# arduino_uno_pcb__with_lcd.net
KiCad netlist of a schematic drawn in EAGLE
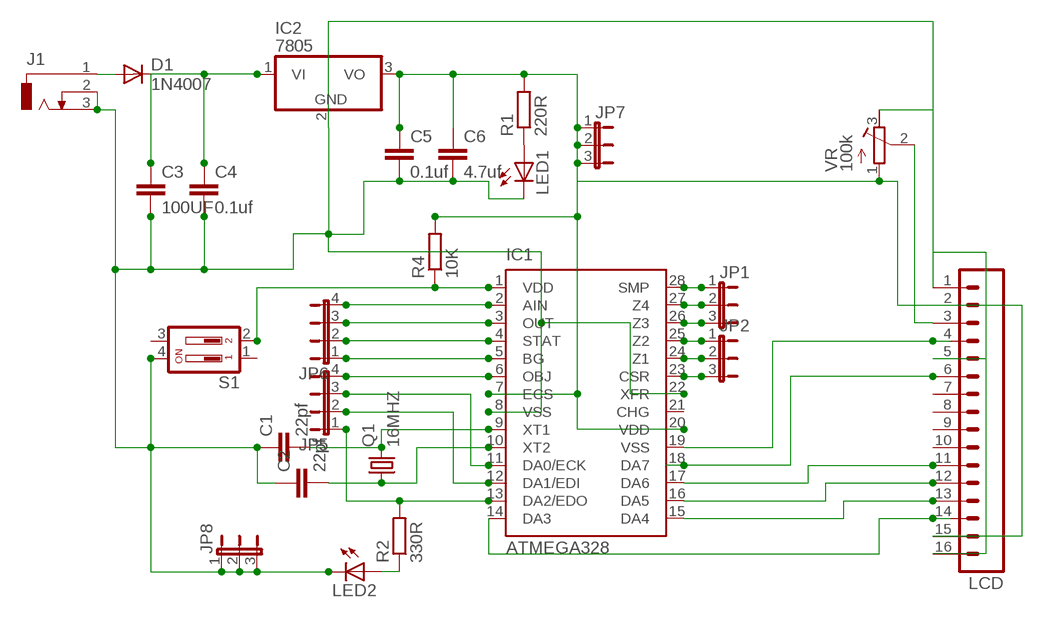
[diagram p0: schematic, sheet 1]

(export (version "E")
  (design (tool "Eeschema 10.0.6"))
  (components
    (comp (ref "C1")
      (value "22pf")
      (footprint "eagle-import:C2.5-2")
      (libsource (lib "eagle-import") (part "C2.5/2"))
    )
    (comp (ref "C2")
      (value "22pf")
      (footprint "eagle-import:C2.5-2")
      (libsource (lib "eagle-import") (part "C2.5/2"))
    )
    (comp (ref "C3")
      (value "100UF")
      (footprint "eagle-import:C2.5-2")
      (libsource (lib "eagle-import") (part "C2.5/2"))
    )
    (comp (ref "C4")
      (value "0.1uf")
      (footprint "eagle-import:C2.5-2")
      (libsource (lib "eagle-import") (part "C2.5/2"))
    )
    (comp (ref "C5")
      (value "0.1uf")
      (footprint "eagle-import:C2.5-2")
      (libsource (lib "eagle-import") (part "C2.5/2"))
    )
    (comp (ref "C6")
      (value "4.7uf")
      (footprint "eagle-import:C2.5-2")
      (libsource (lib "eagle-import") (part "C2.5/2"))
    )
    (comp (ref "D1")
      (value "1N4007")
      (footprint "eagle-import:DO41-10")
      (libsource (lib "eagle-import") (part "1N4004"))
    )
    (comp (ref "IC1")
      (value "ATMEGA328")
      (footprint "eagle-import:DIL28-3")
      (libsource (lib "eagle-import") (part "QT9701BD"))
    )
    (comp (ref "IC2")
      (value "7805")
      (footprint "eagle-import:TO220V")
      (libsource (lib "eagle-import") (part "78TV6"))
    )
    (comp (ref "J1")
      (value "DCJ0303")
      (footprint "eagle-import:DCJ0303")
      (libsource (lib "eagle-import") (part "DCJ0303"))
    )
    (comp (ref "JP1")
      (value "JP2E")
      (footprint "eagle-import:JP2")
      (libsource (lib "eagle-import") (part "JP2E"))
    )
    (comp (ref "JP2")
      (value "JP2E")
      (footprint "eagle-import:JP2")
      (libsource (lib "eagle-import") (part "JP2E"))
    )
    (comp (ref "JP5")
      (value "JP4E")
      (footprint "eagle-import:JP4")
      (libsource (lib "eagle-import") (part "JP4E"))
    )
    (comp (ref "JP6")
      (value "JP4E")
      (footprint "eagle-import:JP4")
      (libsource (lib "eagle-import") (part "JP4E"))
    )
    (comp (ref "JP7")
      (value "JP2E")
      (footprint "eagle-import:JP2")
      (libsource (lib "eagle-import") (part "JP2E"))
    )
    (comp (ref "JP8")
      (value "JP2E")
      (footprint "eagle-import:JP2")
      (libsource (lib "eagle-import") (part "JP2E"))
    )
    (comp (ref "LCD")
      (value "M16")
      (footprint "eagle-import:16P")
      (libsource (lib "eagle-import") (part "M16"))
    )
    (comp (ref "LED1")
      (value "LED3MM")
      (footprint "eagle-import:LED3MM")
      (libsource (lib "eagle-import") (part "LED3MM"))
    )
    (comp (ref "LED2")
      (value "LED3MM")
      (footprint "eagle-import:LED3MM")
      (libsource (lib "eagle-import") (part "LED3MM"))
    )
    (comp (ref "Q1")
      (value "16MHZ")
      (footprint "eagle-import:HC49_S")
      (libsource (lib "eagle-import") (part "CRYSTALHC49S"))
    )
    (comp (ref "R1")
      (value "220R")
      (footprint "eagle-import:0207_10")
      (libsource (lib "eagle-import") (part "R-EU_0207/10"))
    )
    (comp (ref "R2")
      (value "330R")
      (footprint "eagle-import:0207_10")
      (libsource (lib "eagle-import") (part "R-EU_0207/10"))
    )
    (comp (ref "R4")
      (value "10K")
      (footprint "eagle-import:0207_10")
      (libsource (lib "eagle-import") (part "R-EU_0207/10"))
    )
    (comp (ref "S1")
      (value "DP02")
      (footprint "eagle-import:DP-02")
      (fields (field (name "MPN") "MCDP02"))
      (libsource (lib "eagle-import") (part "DP02"))
    )
    (comp (ref "VR")
      (value "100k")
      (footprint "eagle-import:RTRIM64P")
      (libsource (lib "eagle-import") (part "R-TRIMM64P"))
    )
  )
  (nets
    (net (code "1") (name "Net-(D1-PadA)") (class "Default")
      (node (ref "D1") (pin "A") (pinfunction "A_A") (pintype "passive"))
      (node (ref "J1") (pin "1") (pinfunction "1_1") (pintype "passive"))
    )
    (net (code "2") (name "Net-(IC1-AIN)") (class "Default")
      (node (ref "IC1") (pin "2") (pinfunction "AIN_2") (pintype "input"))
      (node (ref "JP6") (pin "4") (pinfunction "4_4") (pintype "passive"))
    )
    (net (code "3") (name "Net-(IC1-BG)") (class "Default")
      (node (ref "IC1") (pin "5") (pinfunction "BG_5") (pintype "input"))
      (node (ref "JP6") (pin "1") (pinfunction "1_1") (pintype "passive"))
    )
    (net (code "4") (name "Net-(IC1-CSR)") (class "Default")
      (node (ref "IC1") (pin "23") (pinfunction "CSR_23") (pintype "output"))
      (node (ref "JP2") (pin "3") (pinfunction "3_3") (pintype "passive"))
    )
    (net (code "5") (name "Net-(IC1-DA0{slash}ECK)") (class "Default")
      (node (ref "IC1") (pin "11") (pinfunction "DA0/ECK_11") (pintype "output"))
      (node (ref "JP5") (pin "3") (pinfunction "3_3") (pintype "passive"))
    )
    (net (code "6") (name "Net-(IC1-DA1{slash}EDI)") (class "Default")
      (node (ref "IC1") (pin "12") (pinfunction "DA1/EDI_12") (pintype "output"))
      (node (ref "JP5") (pin "2") (pinfunction "2_2") (pintype "passive"))
    )
    (net (code "7") (name "Net-(IC1-DA2{slash}EDO)") (class "Default")
      (node (ref "IC1") (pin "13") (pinfunction "DA2/EDO_13") (pintype "output"))
      (node (ref "JP5") (pin "1") (pinfunction "1_1") (pintype "passive"))
      (node (ref "R2") (pin "2") (pinfunction "2_2") (pintype "passive"))
    )
    (net (code "8") (name "Net-(IC1-DA3)") (class "Default")
      (node (ref "IC1") (pin "14") (pinfunction "DA3_14") (pintype "output"))
      (node (ref "LCD") (pin "14") (pinfunction "14_14") (pintype "passive"))
    )
    (net (code "9") (name "Net-(IC1-DA4)") (class "Default")
      (node (ref "IC1") (pin "15") (pinfunction "DA4_15") (pintype "output"))
      (node (ref "LCD") (pin "13") (pinfunction "13_13") (pintype "passive"))
    )
    (net (code "10") (name "Net-(IC1-DA5)") (class "Default")
      (node (ref "IC1") (pin "16") (pinfunction "DA5_16") (pintype "output"))
      (node (ref "LCD") (pin "12") (pinfunction "12_12") (pintype "passive"))
    )
    (net (code "11") (name "Net-(IC1-DA6)") (class "Default")
      (node (ref "IC1") (pin "17") (pinfunction "DA6_17") (pintype "output"))
      (node (ref "LCD") (pin "11") (pinfunction "11_11") (pintype "passive"))
    )
    (net (code "12") (name "Net-(IC1-DA7)") (class "Default")
      (node (ref "IC1") (pin "18") (pinfunction "DA7_18") (pintype "output"))
      (node (ref "LCD") (pin "6") (pinfunction "6_6") (pintype "passive"))
    )
    (net (code "13") (name "Net-(IC1-ECS)") (class "Default")
      (node (ref "C5") (pin "1") (pinfunction "1_1") (pintype "passive"))
      (node (ref "C6") (pin "1") (pinfunction "1_1") (pintype "passive"))
      (node (ref "IC1") (pin "20") (pinfunction "VDD_20") (pintype "input"))
      (node (ref "IC1") (pin "7") (pinfunction "ECS_7") (pintype "output"))
      (node (ref "IC2") (pin "3") (pinfunction "VO_3") (pintype "passive"))
      (node (ref "JP7") (pin "1") (pinfunction "1_1") (pintype "passive"))
      (node (ref "JP7") (pin "2") (pinfunction "2_2") (pintype "passive"))
      (node (ref "JP7") (pin "3") (pinfunction "3_3") (pintype "passive"))
      (node (ref "LCD") (pin "15") (pinfunction "15_15") (pintype "passive"))
      (node (ref "R1") (pin "2") (pinfunction "2_2") (pintype "passive"))
      (node (ref "R4") (pin "2") (pinfunction "2_2") (pintype "passive"))
      (node (ref "VR") (pin "1") (pinfunction "E_1") (pintype "passive"))
    )
    (net (code "14") (name "Net-(IC1-OBJ)") (class "Default")
      (node (ref "IC1") (pin "6") (pinfunction "OBJ_6") (pintype "input"))
      (node (ref "JP5") (pin "4") (pinfunction "4_4") (pintype "passive"))
    )
    (net (code "15") (name "Net-(IC1-OUT)") (class "Default")
      (node (ref "IC1") (pin "3") (pinfunction "OUT_3") (pintype "output"))
      (node (ref "JP6") (pin "3") (pinfunction "3_3") (pintype "passive"))
    )
    (net (code "16") (name "Net-(IC1-SMP)") (class "Default")
      (node (ref "IC1") (pin "28") (pinfunction "SMP_28") (pintype "output"))
      (node (ref "JP1") (pin "1") (pinfunction "1_1") (pintype "passive"))
    )
    (net (code "17") (name "Net-(IC1-STAT)") (class "Default")
      (node (ref "IC1") (pin "4") (pinfunction "STAT_4") (pintype "output"))
      (node (ref "JP6") (pin "2") (pinfunction "2_2") (pintype "passive"))
    )
    (net (code "18") (name "Net-(IC1-VDD-Pad1)") (class "Default")
      (node (ref "IC1") (pin "1") (pinfunction "VDD_1") (pintype "input"))
      (node (ref "R4") (pin "1") (pinfunction "1_1") (pintype "passive"))
      (node (ref "S1") (pin "2") (pinfunction "2_2") (pintype "passive"))
    )
    (net (code "19") (name "Net-(IC1-VSS-Pad19)") (class "Default")
      (node (ref "IC1") (pin "19") (pinfunction "VSS_19") (pintype "input"))
      (node (ref "LCD") (pin "4") (pinfunction "4_4") (pintype "passive"))
    )
    (net (code "20") (name "Net-(IC1-XFR)") (class "Default")
      (node (ref "C1") (pin "1") (pinfunction "1_1") (pintype "passive"))
      (node (ref "C2") (pin "1") (pinfunction "1_1") (pintype "passive"))
      (node (ref "C3") (pin "2") (pinfunction "2_2") (pintype "passive"))
      (node (ref "C4") (pin "2") (pinfunction "2_2") (pintype "passive"))
      (node (ref "C5") (pin "2") (pinfunction "2_2") (pintype "passive"))
      (node (ref "C6") (pin "2") (pinfunction "2_2") (pintype "passive"))
      (node (ref "IC1") (pin "22") (pinfunction "XFR_22") (pintype "output"))
      (node (ref "IC1") (pin "8") (pinfunction "VSS_8") (pintype "input"))
      (node (ref "IC2") (pin "2") (pinfunction "GND_2") (pintype "passive"))
      (node (ref "J1") (pin "2") (pinfunction "2_2") (pintype "passive"))
      (node (ref "J1") (pin "3") (pinfunction "3_3") (pintype "passive"))
      (node (ref "JP8") (pin "1") (pinfunction "1_1") (pintype "passive"))
      (node (ref "JP8") (pin "2") (pinfunction "2_2") (pintype "passive"))
      (node (ref "JP8") (pin "3") (pinfunction "3_3") (pintype "passive"))
      (node (ref "LCD") (pin "1") (pinfunction "1_1") (pintype "passive"))
      (node (ref "LCD") (pin "16") (pinfunction "16_16") (pintype "passive"))
      (node (ref "LCD") (pin "5") (pinfunction "5_5") (pintype "passive"))
      (node (ref "LED1") (pin "K") (pinfunction "C_K") (pintype "passive"))
      (node (ref "LED2") (pin "K") (pinfunction "C_K") (pintype "passive"))
      (node (ref "S1") (pin "4") (pinfunction "4_4") (pintype "passive"))
      (node (ref "VR") (pin "3") (pinfunction "A_3") (pintype "passive"))
    )
    (net (code "21") (name "Net-(IC1-XT1)") (class "Default")
      (node (ref "C1") (pin "2") (pinfunction "2_2") (pintype "passive"))
      (node (ref "IC1") (pin "9") (pinfunction "XT1_9") (pintype "input"))
      (node (ref "Q1") (pin "2") (pinfunction "2_2") (pintype "passive"))
    )
    (net (code "22") (name "Net-(IC1-XT2)") (class "Default")
      (node (ref "C2") (pin "2") (pinfunction "2_2") (pintype "passive"))
      (node (ref "IC1") (pin "10") (pinfunction "XT2_10") (pintype "output"))
      (node (ref "Q1") (pin "1") (pinfunction "1_1") (pintype "passive"))
    )
    (net (code "23") (name "Net-(IC1-Z1)") (class "Default")
      (node (ref "IC1") (pin "24") (pinfunction "Z1_24") (pintype "output"))
      (node (ref "JP2") (pin "2") (pinfunction "2_2") (pintype "passive"))
    )
    (net (code "24") (name "Net-(IC1-Z2)") (class "Default")
      (node (ref "IC1") (pin "25") (pinfunction "Z2_25") (pintype "output"))
      (node (ref "JP2") (pin "1") (pinfunction "1_1") (pintype "passive"))
    )
    (net (code "25") (name "Net-(IC1-Z3)") (class "Default")
      (node (ref "IC1") (pin "26") (pinfunction "Z3_26") (pintype "output"))
      (node (ref "JP1") (pin "3") (pinfunction "3_3") (pintype "passive"))
    )
    (net (code "26") (name "Net-(IC1-Z4)") (class "Default")
      (node (ref "IC1") (pin "27") (pinfunction "Z4_27") (pintype "output"))
      (node (ref "JP1") (pin "2") (pinfunction "2_2") (pintype "passive"))
    )
    (net (code "27") (name "Net-(IC2-VI)") (class "Default")
      (node (ref "C3") (pin "1") (pinfunction "1_1") (pintype "passive"))
      (node (ref "C4") (pin "1") (pinfunction "1_1") (pintype "passive"))
      (node (ref "D1") (pin "C") (pinfunction "C_C") (pintype "passive"))
      (node (ref "IC2") (pin "1") (pinfunction "VI_1") (pintype "input"))
    )
    (net (code "28") (name "Net-(LED1-PadA)") (class "Default")
      (node (ref "LED1") (pin "A") (pinfunction "A_A") (pintype "passive"))
      (node (ref "R1") (pin "1") (pinfunction "1_1") (pintype "passive"))
    )
    (net (code "29") (name "Net-(LED2-PadA)") (class "Default")
      (node (ref "LED2") (pin "A") (pinfunction "A_A") (pintype "passive"))
      (node (ref "R2") (pin "1") (pinfunction "1_1") (pintype "passive"))
    )
    (net (code "30") (name "Net-(VR-S)") (class "Default")
      (node (ref "LCD") (pin "3") (pinfunction "3_3") (pintype "passive"))
      (node (ref "VR") (pin "2") (pinfunction "S_2") (pintype "passive"))
    )
    (net (code "31") (name "unconnected-(IC1-CHG-Pad21)") (class "Default")
      (node (ref "IC1") (pin "21") (pinfunction "CHG_21") (pintype "output"))
    )
    (net (code "32") (name "unconnected-(LCD-Pad2)") (class "Default")
      (node (ref "LCD") (pin "2") (pinfunction "2_2") (pintype "passive"))
    )
    (net (code "33") (name "unconnected-(LCD-Pad7)") (class "Default")
      (node (ref "LCD") (pin "7") (pinfunction "7_7") (pintype "passive"))
    )
    (net (code "34") (name "unconnected-(LCD-Pad8)") (class "Default")
      (node (ref "LCD") (pin "8") (pinfunction "8_8") (pintype "passive"))
    )
    (net (code "35") (name "unconnected-(LCD-Pad9)") (class "Default")
      (node (ref "LCD") (pin "9") (pinfunction "9_9") (pintype "passive"))
    )
    (net (code "36") (name "unconnected-(LCD-Pad10)") (class "Default")
      (node (ref "LCD") (pin "10") (pinfunction "10_10") (pintype "passive"))
    )
    (net (code "37") (name "unconnected-(S1-Pad1)") (class "Default")
      (node (ref "S1") (pin "1") (pinfunction "1_1") (pintype "passive"))
    )
    (net (code "38") (name "unconnected-(S1-Pad3)") (class "Default")
      (node (ref "S1") (pin "3") (pinfunction "3_3") (pintype "passive"))
    )
  )
)
